# Shematic.net
KiCad netlist of a schematic drawn in EAGLE
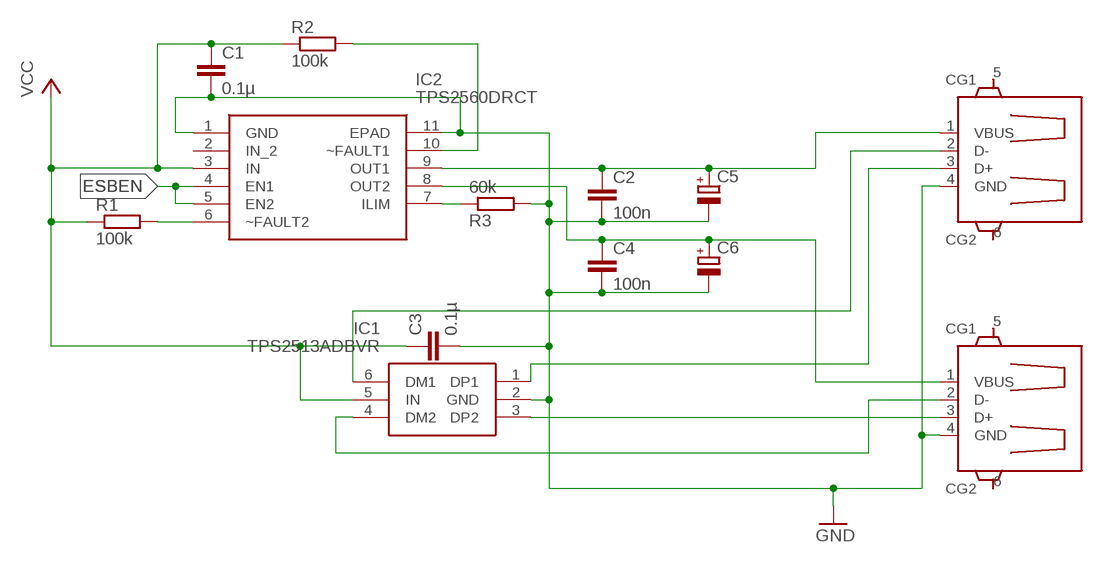
[diagram p0: schematic, sheet 1]

(export (version "E")
  (design (tool "Eeschema 10.0.6"))
  (components
    (comp (ref "C1")
      (value "0.1µ")
      (footprint "eagle-import:C0805")
      (libsource (lib "eagle-import") (part "C-EUC0805"))
    )
    (comp (ref "C2")
      (value "100n")
      (footprint "eagle-import:C1206")
      (libsource (lib "eagle-import") (part "C-EUC1206"))
    )
    (comp (ref "C3")
      (value "0.1µ")
      (footprint "eagle-import:C1206")
      (libsource (lib "eagle-import") (part "C-EUC1206"))
    )
    (comp (ref "C4")
      (value "100n")
      (footprint "eagle-import:C1206")
      (libsource (lib "eagle-import") (part "C-EUC1206"))
    )
    (comp (ref "C5")
      (value "CPOL-EU150CLZ-1010")
      (footprint "eagle-import:150CLZ-1010")
      (libsource (lib "eagle-import") (part "CPOL-EU150CLZ-1010"))
    )
    (comp (ref "C6")
      (value "CPOL-EU150CLZ-1010")
      (footprint "eagle-import:150CLZ-1010")
      (libsource (lib "eagle-import") (part "CPOL-EU150CLZ-1010"))
    )
    (comp (ref "IC1")
      (value "TPS2513ADBVR")
      (footprint "eagle-import:SOT95P280X145-6N")
      (fields (field (name "MOUSER_PART_NUMBER") "595-TPS2513ADBVR"))
      (libsource (lib "eagle-import") (part "TPS2513ADBVR"))
    )
    (comp (ref "IC2")
      (value "TPS2560DRCT")
      (footprint "eagle-import:SON50P300X300X100-11N")
      (fields
        (field (name "MOUSER_PART_NUMBER") "595-TPS2560DRCT")
        (field (name "RS_PART_NUMBER") "8120424P")
      )
      (libsource (lib "eagle-import") (part "TPS2560DRCT"))
    )
    (comp (ref "R1")
      (value "100k")
      (footprint "eagle-import:R1206")
      (libsource (lib "eagle-import") (part "R-EU_R1206"))
    )
    (comp (ref "R2")
      (value "100k")
      (footprint "eagle-import:R1206")
      (libsource (lib "eagle-import") (part "R-EU_R1206"))
    )
    (comp (ref "R3")
      (value "60k")
      (footprint "eagle-import:R1206")
      (libsource (lib "eagle-import") (part "R-EU_R1206"))
    )
    (comp (ref "X1")
      (value "GHI2_USB_HOST_W/CHASSIS_GND")
      (footprint "eagle-import:GHI2_USB_HOST_HORIZONTAL_W_CHASSIS_GND")
      (libsource (lib "eagle-import") (part "GHI2_USB_HOST_W/CHASSIS_GND"))
    )
    (comp (ref "X2")
      (value "GHI2_USB_HOST_W/CHASSIS_GND")
      (footprint "eagle-import:GHI2_USB_HOST_HORIZONTAL_W_CHASSIS_GND")
      (libsource (lib "eagle-import") (part "GHI2_USB_HOST_W/CHASSIS_GND"))
    )
  )
  (nets
    (net (code "1") (name "ESBEN") (class "Default")
      (node (ref "IC2") (pin "4") (pinfunction "EN1_4") (pintype "bidirectional"))
      (node (ref "IC2") (pin "5") (pinfunction "EN2_5") (pintype "bidirectional"))
    )
    (net (code "2") (name "GND") (class "Default")
      (node (ref "C1") (pin "2") (pinfunction "2_2") (pintype "passive"))
      (node (ref "C2") (pin "2") (pinfunction "2_2") (pintype "passive"))
      (node (ref "C3") (pin "2") (pinfunction "2_2") (pintype "passive"))
      (node (ref "C4") (pin "2") (pinfunction "2_2") (pintype "passive"))
      (node (ref "C5") (pin "-") (pinfunction "-_-") (pintype "passive"))
      (node (ref "C6") (pin "-") (pinfunction "-_-") (pintype "passive"))
      (node (ref "IC1") (pin "2") (pinfunction "GND_2") (pintype "power_in"))
      (node (ref "IC2") (pin "1") (pinfunction "GND_1") (pintype "bidirectional"))
      (node (ref "IC2") (pin "11") (pinfunction "EPAD_11") (pintype "bidirectional"))
      (node (ref "R3") (pin "2") (pinfunction "2_2") (pintype "passive"))
      (node (ref "X1") (pin "4") (pinfunction "GND_4") (pintype "bidirectional"))
      (node (ref "X2") (pin "4") (pinfunction "GND_4") (pintype "bidirectional"))
    )
    (net (code "3") (name "Net-(IC1-DM1)") (class "Default")
      (node (ref "IC1") (pin "6") (pinfunction "DM1_6") (pintype "bidirectional"))
      (node (ref "X1") (pin "2") (pinfunction "D-_2") (pintype "bidirectional"))
    )
    (net (code "4") (name "Net-(IC1-DM2)") (class "Default")
      (node (ref "IC1") (pin "4") (pinfunction "DM2_4") (pintype "bidirectional"))
      (node (ref "X2") (pin "2") (pinfunction "D-_2") (pintype "bidirectional"))
    )
    (net (code "5") (name "Net-(IC1-DP1)") (class "Default")
      (node (ref "IC1") (pin "1") (pinfunction "DP1_1") (pintype "bidirectional"))
      (node (ref "X1") (pin "3") (pinfunction "D+_3") (pintype "bidirectional"))
    )
    (net (code "6") (name "Net-(IC1-DP2)") (class "Default")
      (node (ref "IC1") (pin "3") (pinfunction "DP2_3") (pintype "bidirectional"))
      (node (ref "X2") (pin "3") (pinfunction "D+_3") (pintype "bidirectional"))
    )
    (net (code "7") (name "Net-(IC2-ILIM)") (class "Default")
      (node (ref "IC2") (pin "7") (pinfunction "ILIM_7") (pintype "bidirectional"))
      (node (ref "R3") (pin "1") (pinfunction "1_1") (pintype "passive"))
    )
    (net (code "8") (name "Net-(IC2-OUT1)") (class "Default")
      (node (ref "C2") (pin "1") (pinfunction "1_1") (pintype "passive"))
      (node (ref "C5") (pin "+") (pinfunction "+_+") (pintype "passive"))
      (node (ref "IC2") (pin "9") (pinfunction "OUT1_9") (pintype "bidirectional"))
      (node (ref "X1") (pin "1") (pinfunction "VBUS_1") (pintype "bidirectional"))
    )
    (net (code "9") (name "Net-(IC2-OUT2)") (class "Default")
      (node (ref "C4") (pin "1") (pinfunction "1_1") (pintype "passive"))
      (node (ref "C6") (pin "+") (pinfunction "+_+") (pintype "passive"))
      (node (ref "IC2") (pin "8") (pinfunction "OUT2_8") (pintype "bidirectional"))
      (node (ref "X2") (pin "1") (pinfunction "VBUS_1") (pintype "bidirectional"))
    )
    (net (code "10") (name "Net-(IC2-~{FAULT1})") (class "Default")
      (node (ref "IC2") (pin "10") (pinfunction "~{FAULT1}_10") (pintype "bidirectional"))
      (node (ref "R2") (pin "2") (pinfunction "2_2") (pintype "passive"))
    )
    (net (code "11") (name "Net-(IC2-~{FAULT2})") (class "Default")
      (node (ref "IC2") (pin "6") (pinfunction "~{FAULT2}_6") (pintype "bidirectional"))
      (node (ref "R1") (pin "2") (pinfunction "2_2") (pintype "passive"))
    )
    (net (code "12") (name "VCC") (class "Default")
      (node (ref "C1") (pin "1") (pinfunction "1_1") (pintype "passive"))
      (node (ref "C3") (pin "1") (pinfunction "1_1") (pintype "passive"))
      (node (ref "IC1") (pin "5") (pinfunction "IN_5") (pintype "power_in"))
      (node (ref "IC2") (pin "3") (pinfunction "IN_3") (pintype "bidirectional"))
      (node (ref "R1") (pin "1") (pinfunction "1_1") (pintype "passive"))
      (node (ref "R2") (pin "1") (pinfunction "1_1") (pintype "passive"))
    )
    (net (code "13") (name "unconnected-(IC2-IN_2-Pad2)") (class "Default")
      (node (ref "IC2") (pin "2") (pinfunction "IN_2_2") (pintype "bidirectional"))
    )
    (net (code "14") (name "unconnected-(X1-CG1-Pad5)") (class "Default")
      (node (ref "X1") (pin "5") (pinfunction "CG1_5") (pintype "bidirectional"))
    )
    (net (code "15") (name "unconnected-(X1-CG2-Pad6)") (class "Default")
      (node (ref "X1") (pin "6") (pinfunction "CG2_6") (pintype "bidirectional"))
    )
    (net (code "16") (name "unconnected-(X2-CG1-Pad5)") (class "Default")
      (node (ref "X2") (pin "5") (pinfunction "CG1_5") (pintype "bidirectional"))
    )
    (net (code "17") (name "unconnected-(X2-CG2-Pad6)") (class "Default")
      (node (ref "X2") (pin "6") (pinfunction "CG2_6") (pintype "bidirectional"))
    )
  )
)
